# main.net
KiCad netlist of a schematic drawn in EAGLE
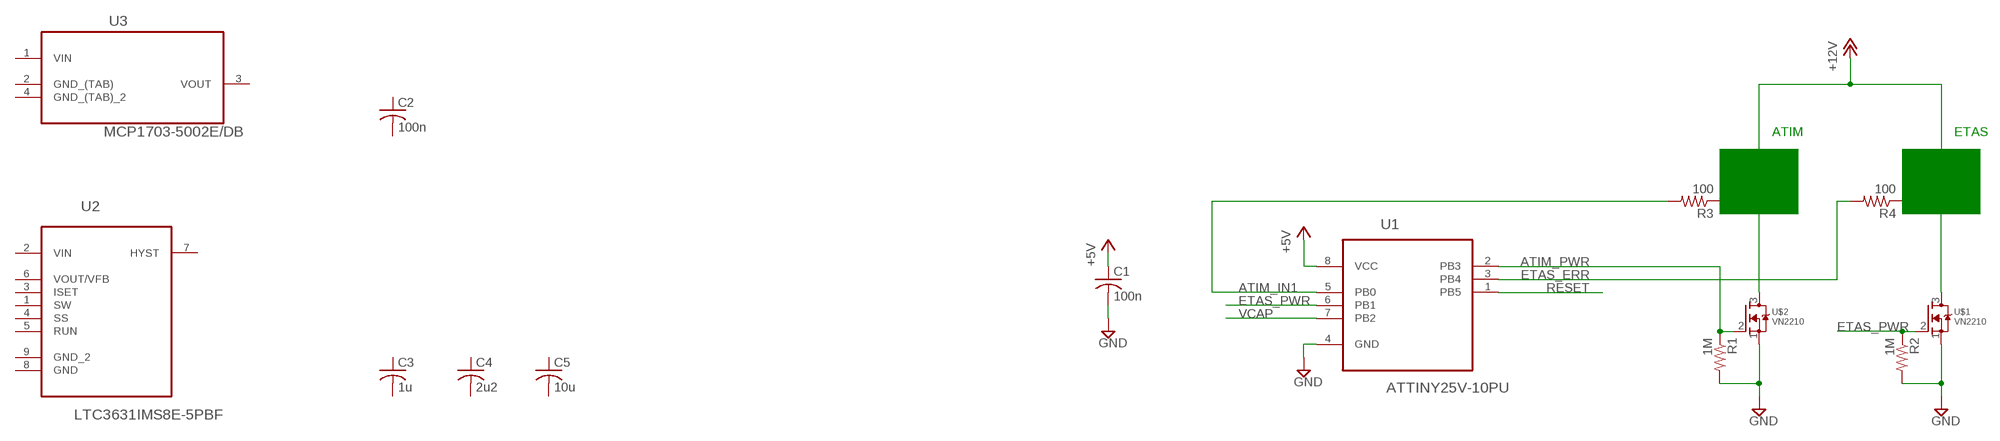
[diagram p0: schematic, sheet 1]

(export (version "E")
  (design (tool "Eeschema 10.0.6"))
  (components
    (comp (ref "C1")
      (value "100n")
      (footprint "eagle-import:C0805")
      (libsource (lib "eagle-import") (part "C-USC0805"))
    )
    (comp (ref "C2")
      (value "100n")
      (footprint "eagle-import:C0805")
      (libsource (lib "eagle-import") (part "C-USC0805"))
    )
    (comp (ref "C3")
      (value "1u")
      (footprint "eagle-import:C0805")
      (libsource (lib "eagle-import") (part "C-USC0805"))
    )
    (comp (ref "C4")
      (value "2u2")
      (footprint "eagle-import:C0805")
      (libsource (lib "eagle-import") (part "C-USC0805"))
    )
    (comp (ref "C5")
      (value "10u")
      (footprint "eagle-import:C0805")
      (libsource (lib "eagle-import") (part "C-USC0805"))
    )
    (comp (ref "R1")
      (value "1M")
      (footprint "eagle-import:M0805")
      (libsource (lib "eagle-import") (part "R-US_M0805"))
    )
    (comp (ref "R2")
      (value "1M")
      (footprint "eagle-import:M0805")
      (libsource (lib "eagle-import") (part "R-US_M0805"))
    )
    (comp (ref "R3")
      (value "100")
      (footprint "eagle-import:M0805")
      (libsource (lib "eagle-import") (part "R-US_M0805"))
    )
    (comp (ref "R4")
      (value "100")
      (footprint "eagle-import:M0805")
      (libsource (lib "eagle-import") (part "R-US_M0805"))
    )
    (comp (ref "U$1")
      (value "VN2210")
      (footprint "eagle-import:TO92")
      (libsource (lib "eagle-import") (part "VN2210"))
    )
    (comp (ref "U$2")
      (value "VN2210")
      (footprint "eagle-import:TO92")
      (libsource (lib "eagle-import") (part "VN2210"))
    )
    (comp (ref "U1")
      (value "ATTINY25V-10PU")
      (footprint "eagle-import:DIP254P762X533-8")
      (libsource (lib "eagle-import") (part "ATTINY25V-10PU"))
    )
    (comp (ref "U2")
      (value "LTC3631IMS8E-5PBF")
      (footprint "eagle-import:SOP65P490X110-9N")
      (fields (field (name "MPN") "LTC3631IMS8E-5#PBF"))
      (libsource (lib "eagle-import") (part "LTC3631IMS8E-5PBF"))
    )
    (comp (ref "U3")
      (value "MCP1703-5002E/DB")
      (footprint "eagle-import:SOT230P700X180-4N")
      (libsource (lib "eagle-import") (part "MCP1703-5002E/DB"))
    )
  )
  (nets
    (net (code "1") (name "+5V") (class "Default")
      (node (ref "C1") (pin "1") (pinfunction "1_1") (pintype "passive"))
      (node (ref "U1") (pin "8") (pinfunction "VCC_8") (pintype "power_in"))
    )
    (net (code "3") (name "/ATIM_IN1") (class "Default")
      (node (ref "R3") (pin "2") (pinfunction "2_2") (pintype "passive"))
      (node (ref "U1") (pin "5") (pinfunction "PB0_5") (pintype "bidirectional"))
    )
    (net (code "4") (name "/ATIM_PWR") (class "Default")
      (node (ref "R1") (pin "1") (pinfunction "1_1") (pintype "passive"))
      (node (ref "U$2") (pin "2") (pinfunction "G_2") (pintype "bidirectional"))
      (node (ref "U1") (pin "2") (pinfunction "PB3_2") (pintype "bidirectional"))
    )
    (net (code "5") (name "/ETAS_ERR") (class "Default")
      (node (ref "R4") (pin "2") (pinfunction "2_2") (pintype "passive"))
      (node (ref "U1") (pin "3") (pinfunction "PB4_3") (pintype "bidirectional"))
    )
    (net (code "6") (name "/ETAS_PWR") (class "Default")
      (node (ref "R2") (pin "1") (pinfunction "1_1") (pintype "passive"))
      (node (ref "U$1") (pin "2") (pinfunction "G_2") (pintype "bidirectional"))
      (node (ref "U1") (pin "6") (pinfunction "PB1_6") (pintype "bidirectional"))
    )
    (net (code "7") (name "/RESET") (class "Default")
      (node (ref "U1") (pin "1") (pinfunction "PB5_1") (pintype "bidirectional"))
    )
    (net (code "8") (name "/VCAP") (class "Default")
      (node (ref "U1") (pin "7") (pinfunction "PB2_7") (pintype "bidirectional"))
    )
    (net (code "9") (name "/VIN") (class "Default")
      (node (ref "U2") (pin "2") (pinfunction "VIN_2") (pintype "power_in"))
    )
    (net (code "10") (name "GND") (class "Default")
      (node (ref "C1") (pin "2") (pinfunction "2_2") (pintype "passive"))
      (node (ref "R1") (pin "2") (pinfunction "2_2") (pintype "passive"))
      (node (ref "R2") (pin "2") (pinfunction "2_2") (pintype "passive"))
      (node (ref "U$1") (pin "1") (pinfunction "S_1") (pintype "bidirectional"))
      (node (ref "U$2") (pin "1") (pinfunction "S_1") (pintype "bidirectional"))
      (node (ref "U1") (pin "4") (pinfunction "GND_4") (pintype "passive"))
    )
    (net (code "11") (name "unconnected-(C2-Pad1)") (class "Default")
      (node (ref "C2") (pin "1") (pinfunction "1_1") (pintype "passive"))
    )
    (net (code "12") (name "unconnected-(C2-Pad2)") (class "Default")
      (node (ref "C2") (pin "2") (pinfunction "2_2") (pintype "passive"))
    )
    (net (code "13") (name "unconnected-(C3-Pad1)") (class "Default")
      (node (ref "C3") (pin "1") (pinfunction "1_1") (pintype "passive"))
    )
    (net (code "14") (name "unconnected-(C3-Pad2)") (class "Default")
      (node (ref "C3") (pin "2") (pinfunction "2_2") (pintype "passive"))
    )
    (net (code "15") (name "unconnected-(C4-Pad1)") (class "Default")
      (node (ref "C4") (pin "1") (pinfunction "1_1") (pintype "passive"))
    )
    (net (code "16") (name "unconnected-(C4-Pad2)") (class "Default")
      (node (ref "C4") (pin "2") (pinfunction "2_2") (pintype "passive"))
    )
    (net (code "17") (name "unconnected-(C5-Pad1)") (class "Default")
      (node (ref "C5") (pin "1") (pinfunction "1_1") (pintype "passive"))
    )
    (net (code "18") (name "unconnected-(C5-Pad2)") (class "Default")
      (node (ref "C5") (pin "2") (pinfunction "2_2") (pintype "passive"))
    )
    (net (code "19") (name "unconnected-(R3-Pad1)") (class "Default")
      (node (ref "R3") (pin "1") (pinfunction "1_1") (pintype "passive"))
    )
    (net (code "20") (name "unconnected-(R4-Pad1)") (class "Default")
      (node (ref "R4") (pin "1") (pinfunction "1_1") (pintype "passive"))
    )
    (net (code "21") (name "unconnected-(U$1-D-Pad3)") (class "Default")
      (node (ref "U$1") (pin "3") (pinfunction "D_3") (pintype "bidirectional"))
    )
    (net (code "22") (name "unconnected-(U$2-D-Pad3)") (class "Default")
      (node (ref "U$2") (pin "3") (pinfunction "D_3") (pintype "bidirectional"))
    )
    (net (code "23") (name "unconnected-(U2-GND-Pad8)") (class "Default")
      (node (ref "U2") (pin "8") (pinfunction "GND_8") (pintype "passive"))
    )
    (net (code "24") (name "unconnected-(U2-GND_2-Pad9)") (class "Default")
      (node (ref "U2") (pin "9") (pinfunction "GND_2_9") (pintype "passive"))
    )
    (net (code "25") (name "unconnected-(U2-HYST-Pad7)") (class "Default")
      (node (ref "U2") (pin "7") (pinfunction "HYST_7") (pintype "output"))
    )
    (net (code "26") (name "unconnected-(U2-ISET-Pad3)") (class "Default")
      (node (ref "U2") (pin "3") (pinfunction "ISET_3") (pintype "input"))
    )
    (net (code "27") (name "unconnected-(U2-RUN-Pad5)") (class "Default")
      (node (ref "U2") (pin "5") (pinfunction "RUN_5") (pintype "input"))
    )
    (net (code "28") (name "unconnected-(U2-SS-Pad4)") (class "Default")
      (node (ref "U2") (pin "4") (pinfunction "SS_4") (pintype "input"))
    )
    (net (code "29") (name "unconnected-(U2-SW-Pad1)") (class "Default")
      (node (ref "U2") (pin "1") (pinfunction "SW_1") (pintype "passive"))
    )
    (net (code "30") (name "unconnected-(U2-VOUT{slash}VFB-Pad6)") (class "Default")
      (node (ref "U2") (pin "6") (pinfunction "VOUT/VFB_6") (pintype "input"))
    )
    (net (code "31") (name "unconnected-(U3-GND_(TAB)-Pad2)") (class "Default")
      (node (ref "U3") (pin "2") (pinfunction "GND_(TAB)_2") (pintype "passive"))
    )
    (net (code "32") (name "unconnected-(U3-GND_(TAB)_2-Pad4)") (class "Default")
      (node (ref "U3") (pin "4") (pinfunction "GND_(TAB)_2_4") (pintype "passive"))
    )
    (net (code "33") (name "unconnected-(U3-VIN-Pad1)") (class "Default")
      (node (ref "U3") (pin "1") (pinfunction "VIN_1") (pintype "input"))
    )
    (net (code "34") (name "unconnected-(U3-VOUT-Pad3)") (class "Default")
      (node (ref "U3") (pin "3") (pinfunction "VOUT_3") (pintype "output"))
    )
  )
)
